# Attenuator_10x100x.net
KiCad netlist of a schematic drawn in Altium Designer
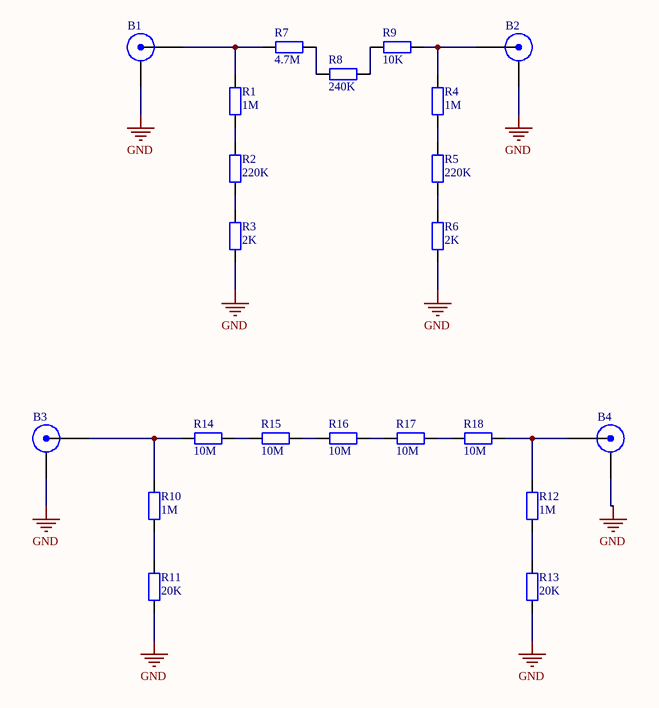
[diagram p0: Attenuator_10x100x.SchDoc]

(export (version "E")
  (design (tool "Eeschema 10.0.6"))
  (components
    (comp (ref "B1")
      (value "BNC")
      (footprint "BNC-5P")
      (description "BNC Connector")
      (fields (field (name "PUBLISHER") "Altium Limited"))
      (libsource (lib "Connectors") (part "BNC_1"))
    )
    (comp (ref "B2")
      (value "BNC")
      (footprint "BNC-5P")
      (description "BNC Connector")
      (fields (field (name "PUBLISHER") "Altium Limited"))
      (libsource (lib "Connectors") (part "BNC_1"))
    )
    (comp (ref "B3")
      (value "BNC")
      (footprint "BNC-5P")
      (description "BNC Connector")
      (fields (field (name "PUBLISHER") "Altium Limited"))
      (libsource (lib "Connectors") (part "BNC_1"))
    )
    (comp (ref "B4")
      (value "BNC")
      (footprint "BNC-5P")
      (description "BNC Connector")
      (fields (field (name "PUBLISHER") "Altium Limited"))
      (libsource (lib "Connectors") (part "BNC_1"))
    )
    (comp (ref "R1")
      (value "1M")
      (footprint "RS 1/4W")
      (description "直插色环电阻")
      (fields (field (name "版权归属") "源创客"))
      (libsource (lib "电阻-电容-电感") (part "R-CRR"))
    )
    (comp (ref "R2")
      (value "220K")
      (footprint "RS 1/4W")
      (description "直插色环电阻")
      (fields (field (name "版权归属") "源创客"))
      (libsource (lib "电阻-电容-电感") (part "R-CRR"))
    )
    (comp (ref "R3")
      (value "2K")
      (footprint "RS 1/4W")
      (description "直插色环电阻")
      (fields (field (name "版权归属") "源创客"))
      (libsource (lib "电阻-电容-电感") (part "R-CRR"))
    )
    (comp (ref "R4")
      (value "1M")
      (footprint "RS 1/4W")
      (description "直插色环电阻")
      (fields (field (name "版权归属") "源创客"))
      (libsource (lib "电阻-电容-电感") (part "R-CRR"))
    )
    (comp (ref "R5")
      (value "220K")
      (footprint "RS 1/4W")
      (description "直插色环电阻")
      (fields (field (name "版权归属") "源创客"))
      (libsource (lib "电阻-电容-电感") (part "R-CRR"))
    )
    (comp (ref "R6")
      (value "2K")
      (footprint "RS 1/4W")
      (description "直插色环电阻")
      (fields (field (name "版权归属") "源创客"))
      (libsource (lib "电阻-电容-电感") (part "R-CRR"))
    )
    (comp (ref "R7")
      (value "4.7M")
      (footprint "RS 1/4W")
      (description "直插色环电阻")
      (fields (field (name "版权归属") "源创客"))
      (libsource (lib "电阻-电容-电感") (part "R-CRR"))
    )
    (comp (ref "R8")
      (value "240K")
      (footprint "RS 1/4W")
      (description "直插色环电阻")
      (fields (field (name "版权归属") "源创客"))
      (libsource (lib "电阻-电容-电感") (part "R-CRR"))
    )
    (comp (ref "R9")
      (value "10K")
      (footprint "RS 1/4W")
      (description "直插色环电阻")
      (fields (field (name "版权归属") "源创客"))
      (libsource (lib "电阻-电容-电感") (part "R-CRR"))
    )
    (comp (ref "R10")
      (value "1M")
      (footprint "RS 1/4W")
      (description "直插色环电阻")
      (fields (field (name "版权归属") "源创客"))
      (libsource (lib "电阻-电容-电感") (part "R-CRR"))
    )
    (comp (ref "R11")
      (value "20K")
      (footprint "RS 1/4W")
      (description "直插色环电阻")
      (fields (field (name "版权归属") "源创客"))
      (libsource (lib "电阻-电容-电感") (part "R-CRR"))
    )
    (comp (ref "R12")
      (value "1M")
      (footprint "RS 1/4W")
      (description "直插色环电阻")
      (fields (field (name "版权归属") "源创客"))
      (libsource (lib "电阻-电容-电感") (part "R-CRR"))
    )
    (comp (ref "R13")
      (value "20K")
      (footprint "RS 1/4W")
      (description "直插色环电阻")
      (fields (field (name "版权归属") "源创客"))
      (libsource (lib "电阻-电容-电感") (part "R-CRR"))
    )
    (comp (ref "R14")
      (value "10M")
      (footprint "RS 1/4W")
      (description "直插色环电阻")
      (fields (field (name "版权归属") "源创客"))
      (libsource (lib "电阻-电容-电感") (part "R-CRR"))
    )
    (comp (ref "R15")
      (value "10M")
      (footprint "RS 1/4W")
      (description "直插色环电阻")
      (fields (field (name "版权归属") "源创客"))
      (libsource (lib "电阻-电容-电感") (part "R-CRR"))
    )
    (comp (ref "R16")
      (value "10M")
      (footprint "RS 1/4W")
      (description "直插色环电阻")
      (fields (field (name "版权归属") "源创客"))
      (libsource (lib "电阻-电容-电感") (part "R-CRR"))
    )
    (comp (ref "R17")
      (value "10M")
      (footprint "RS 1/4W")
      (description "直插色环电阻")
      (fields (field (name "版权归属") "源创客"))
      (libsource (lib "电阻-电容-电感") (part "R-CRR"))
    )
    (comp (ref "R18")
      (value "10M")
      (footprint "RS 1/4W")
      (description "直插色环电阻")
      (fields (field (name "版权归属") "源创客"))
      (libsource (lib "电阻-电容-电感") (part "R-CRR"))
    )
  )
  (nets
    (net (code "1") (name "GND") (class "Default")
      (node (ref "B1") (pin "2") (pinfunction "Y_2") (pintype "passive"))
      (node (ref "B2") (pin "2") (pinfunction "Y_2") (pintype "passive"))
      (node (ref "B3") (pin "2") (pinfunction "Y_2") (pintype "passive"))
      (node (ref "B4") (pin "2") (pinfunction "Y_2") (pintype "passive"))
      (node (ref "R11") (pin "1") (pinfunction "1_1") (pintype "passive"))
      (node (ref "R13") (pin "1") (pinfunction "1_1") (pintype "passive"))
      (node (ref "R3") (pin "1") (pinfunction "1_1") (pintype "passive"))
      (node (ref "R6") (pin "2") (pinfunction "2_2") (pintype "passive"))
    )
    (net (code "2") (name "Net-(B1-X)") (class "Default")
      (node (ref "B1") (pin "1") (pinfunction "X_1") (pintype "passive"))
      (node (ref "R1") (pin "2") (pinfunction "2_2") (pintype "passive"))
      (node (ref "R7") (pin "1") (pinfunction "1_1") (pintype "passive"))
    )
    (net (code "3") (name "Net-(B2-X)") (class "Default")
      (node (ref "B2") (pin "1") (pinfunction "X_1") (pintype "passive"))
      (node (ref "R4") (pin "2") (pinfunction "2_2") (pintype "passive"))
      (node (ref "R9") (pin "2") (pinfunction "2_2") (pintype "passive"))
    )
    (net (code "4") (name "Net-(B3-X)") (class "Default")
      (node (ref "B3") (pin "1") (pinfunction "X_1") (pintype "passive"))
      (node (ref "R10") (pin "2") (pinfunction "2_2") (pintype "passive"))
      (node (ref "R14") (pin "1") (pinfunction "1_1") (pintype "passive"))
    )
    (net (code "5") (name "Net-(B4-X)") (class "Default")
      (node (ref "B4") (pin "1") (pinfunction "X_1") (pintype "passive"))
      (node (ref "R12") (pin "2") (pinfunction "2_2") (pintype "passive"))
      (node (ref "R18") (pin "2") (pinfunction "2_2") (pintype "passive"))
    )
    (net (code "6") (name "Net-(R1-Pad1)") (class "Default")
      (node (ref "R1") (pin "1") (pinfunction "1_1") (pintype "passive"))
      (node (ref "R2") (pin "2") (pinfunction "2_2") (pintype "passive"))
    )
    (net (code "7") (name "Net-(R2-Pad1)") (class "Default")
      (node (ref "R2") (pin "1") (pinfunction "1_1") (pintype "passive"))
      (node (ref "R3") (pin "2") (pinfunction "2_2") (pintype "passive"))
    )
    (net (code "8") (name "Net-(R4-Pad1)") (class "Default")
      (node (ref "R4") (pin "1") (pinfunction "1_1") (pintype "passive"))
      (node (ref "R5") (pin "2") (pinfunction "2_2") (pintype "passive"))
    )
    (net (code "9") (name "Net-(R5-Pad1)") (class "Default")
      (node (ref "R5") (pin "1") (pinfunction "1_1") (pintype "passive"))
      (node (ref "R6") (pin "1") (pinfunction "1_1") (pintype "passive"))
    )
    (net (code "10") (name "Net-(R7-Pad2)") (class "Default")
      (node (ref "R7") (pin "2") (pinfunction "2_2") (pintype "passive"))
      (node (ref "R8") (pin "1") (pinfunction "1_1") (pintype "passive"))
    )
    (net (code "11") (name "Net-(R8-Pad2)") (class "Default")
      (node (ref "R8") (pin "2") (pinfunction "2_2") (pintype "passive"))
      (node (ref "R9") (pin "1") (pinfunction "1_1") (pintype "passive"))
    )
    (net (code "12") (name "Net-(R10-Pad1)") (class "Default")
      (node (ref "R10") (pin "1") (pinfunction "1_1") (pintype "passive"))
      (node (ref "R11") (pin "2") (pinfunction "2_2") (pintype "passive"))
    )
    (net (code "13") (name "Net-(R12-Pad1)") (class "Default")
      (node (ref "R12") (pin "1") (pinfunction "1_1") (pintype "passive"))
      (node (ref "R13") (pin "2") (pinfunction "2_2") (pintype "passive"))
    )
    (net (code "14") (name "Net-(R14-Pad2)") (class "Default")
      (node (ref "R14") (pin "2") (pinfunction "2_2") (pintype "passive"))
      (node (ref "R15") (pin "1") (pinfunction "1_1") (pintype "passive"))
    )
    (net (code "15") (name "Net-(R15-Pad2)") (class "Default")
      (node (ref "R15") (pin "2") (pinfunction "2_2") (pintype "passive"))
      (node (ref "R16") (pin "1") (pinfunction "1_1") (pintype "passive"))
    )
    (net (code "16") (name "Net-(R16-Pad2)") (class "Default")
      (node (ref "R16") (pin "2") (pinfunction "2_2") (pintype "passive"))
      (node (ref "R17") (pin "1") (pinfunction "1_1") (pintype "passive"))
    )
    (net (code "17") (name "Net-(R17-Pad2)") (class "Default")
      (node (ref "R17") (pin "2") (pinfunction "2_2") (pintype "passive"))
      (node (ref "R18") (pin "1") (pinfunction "1_1") (pintype "passive"))
    )
  )
)
